# transmitter.net
KiCad netlist of a schematic drawn in EAGLE
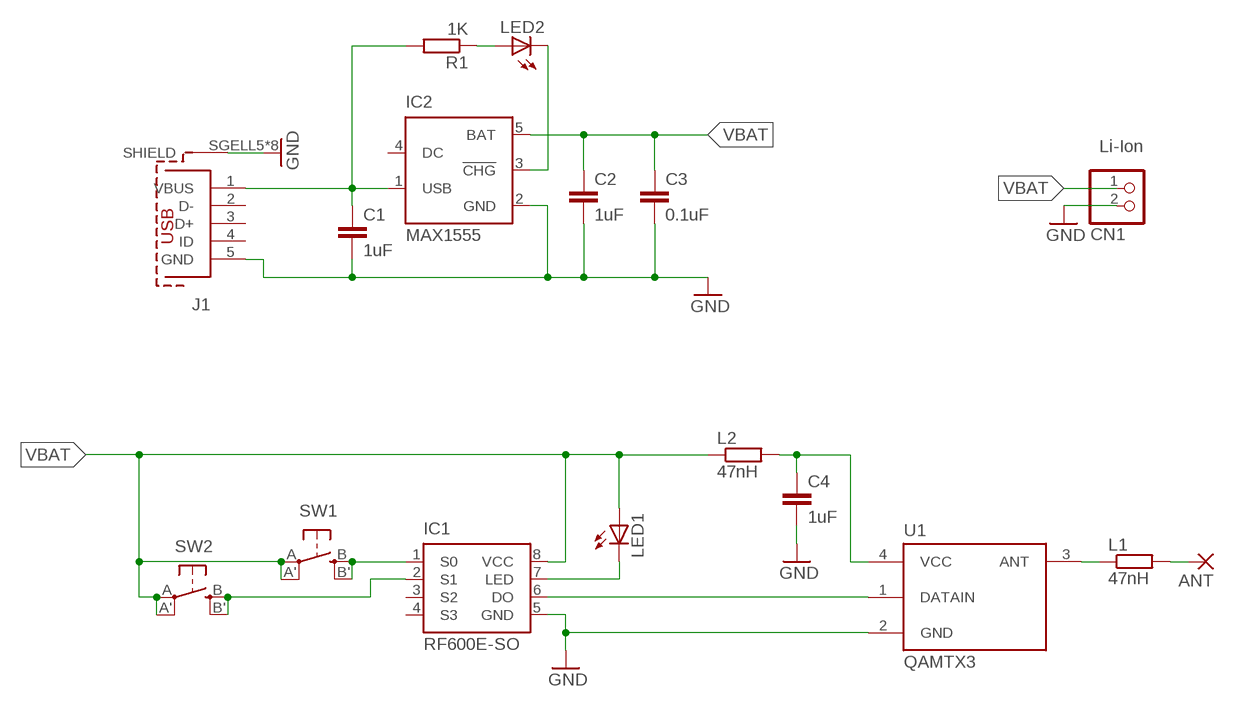
[diagram p0: schematic, sheet 1]

(export (version "E")
  (design (tool "Eeschema 10.0.6"))
  (components
    (comp (ref "ANT")
      (value "SMD2")
      (footprint "eagle-import:SMD1,27-2,54")
      (libsource (lib "eagle-import") (part "SMD2"))
    )
    (comp (ref "C1")
      (value "1uF")
      (footprint "eagle-import:C0603K")
      (libsource (lib "eagle-import") (part "C-EUC0603K"))
    )
    (comp (ref "C2")
      (value "1uF")
      (footprint "eagle-import:C0603K")
      (libsource (lib "eagle-import") (part "C-EUC0603K"))
    )
    (comp (ref "C3")
      (value "0.1uF")
      (footprint "eagle-import:C0603K")
      (libsource (lib "eagle-import") (part "C-EUC0603K"))
    )
    (comp (ref "C4")
      (value "1uF")
      (footprint "eagle-import:C0603K")
      (libsource (lib "eagle-import") (part "C-EUC0603K"))
    )
    (comp (ref "CN1")
      (value "JST_2PIN-SMT-RA")
      (footprint "eagle-import:JST-PH-2-SMT-RA")
      (libsource (lib "eagle-import") (part "JST_2PIN-SMT-RA"))
    )
    (comp (ref "IC1")
      (value "RF600E-SO")
      (footprint "eagle-import:SO-08")
      (fields (field (name "MF") "FARNELL"))
      (libsource (lib "eagle-import") (part "RF600E-SO"))
    )
    (comp (ref "IC2")
      (value "MAX1555")
      (footprint "eagle-import:SOT23-5L")
      (fields (field (name "MF") "MAXIM") (field (name "MPN") "MAX1555EZK+T"))
      (libsource (lib "eagle-import") (part "MAX1555"))
    )
    (comp (ref "J1")
      (value "629105150921")
      (footprint "eagle-import:629105150921")
      (libsource (lib "eagle-import") (part "629105150921"))
    )
    (comp (ref "L1")
      (value "47nH")
      (footprint "eagle-import:R0603")
      (libsource (lib "eagle-import") (part "R-EU_R0603"))
    )
    (comp (ref "L2")
      (value "47nH")
      (footprint "eagle-import:R0603")
      (libsource (lib "eagle-import") (part "R-EU_R0603"))
    )
    (comp (ref "LED1")
      (value "LEDCHIP-LED0805")
      (footprint "eagle-import:CHIP-LED0805")
      (libsource (lib "eagle-import") (part "LEDCHIP-LED0805"))
    )
    (comp (ref "LED2")
      (value "LEDCHIP-LED0805")
      (footprint "eagle-import:CHIP-LED0805")
      (libsource (lib "eagle-import") (part "LEDCHIP-LED0805"))
    )
    (comp (ref "R1")
      (value "1K")
      (footprint "eagle-import:R0603")
      (libsource (lib "eagle-import") (part "R-EU_R0603"))
    )
    (comp (ref "SW1")
      (value "SPST_TACT-EVQQ2")
      (footprint "eagle-import:EVQ-Q2")
      (libsource (lib "eagle-import") (part "SPST_TACT-EVQQ2"))
    )
    (comp (ref "SW2")
      (value "SPST_TACT-EVQQ2")
      (footprint "eagle-import:EVQ-Q2")
      (libsource (lib "eagle-import") (part "SPST_TACT-EVQQ2"))
    )
    (comp (ref "U1")
      (value "QAMTX3")
      (footprint "eagle-import:QAM-TX3")
      (libsource (lib "eagle-import") (part "QAMTX3"))
    )
  )
  (nets
    (net (code "1") (name "GND") (class "Default")
      (node (ref "C1") (pin "2") (pinfunction "2_2") (pintype "passive"))
      (node (ref "C2") (pin "2") (pinfunction "2_2") (pintype "passive"))
      (node (ref "C3") (pin "2") (pinfunction "2_2") (pintype "passive"))
      (node (ref "C4") (pin "2") (pinfunction "2_2") (pintype "passive"))
      (node (ref "CN1") (pin "2") (pinfunction "1_2") (pintype "passive"))
      (node (ref "IC1") (pin "5") (pinfunction "GND_5") (pintype "power_in"))
      (node (ref "IC2") (pin "2") (pinfunction "GND_2") (pintype "power_in"))
      (node (ref "J1") (pin "5") (pinfunction "GND_5") (pintype "passive"))
      (node (ref "J1") (pin "SGELL5") (pinfunction "SHIELD_SGELL5") (pintype "passive"))
      (node (ref "J1") (pin "SHELL") (pinfunction "SHIELD_SHELL") (pintype "passive"))
      (node (ref "J1") (pin "SHELL1") (pinfunction "SHIELD_SHELL1") (pintype "passive"))
      (node (ref "J1") (pin "SHELL2") (pinfunction "SHIELD_SHELL2") (pintype "passive"))
      (node (ref "J1") (pin "SHELL3") (pinfunction "SHIELD_SHELL3") (pintype "passive"))
      (node (ref "J1") (pin "SHELL4") (pinfunction "SHIELD_SHELL4") (pintype "passive"))
      (node (ref "J1") (pin "SHELL6") (pinfunction "SHIELD_SHELL6") (pintype "passive"))
      (node (ref "J1") (pin "SHELL7") (pinfunction "SHIELD_SHELL7") (pintype "passive"))
      (node (ref "U1") (pin "2") (pinfunction "GND_2") (pintype "power_in"))
    )
    (net (code "2") (name "Net-(ANT-P)") (class "Default")
      (node (ref "ANT") (pin "1") (pinfunction "P_1") (pintype "passive"))
      (node (ref "L1") (pin "2") (pinfunction "2_2") (pintype "passive"))
    )
    (net (code "3") (name "Net-(IC1-DO)") (class "Default")
      (node (ref "IC1") (pin "6") (pinfunction "DO_6") (pintype "output"))
      (node (ref "U1") (pin "1") (pinfunction "DATAIN_1") (pintype "bidirectional"))
    )
    (net (code "4") (name "Net-(IC1-LED)") (class "Default")
      (node (ref "IC1") (pin "7") (pinfunction "LED_7") (pintype "output"))
      (node (ref "LED1") (pin "C") (pinfunction "C_C") (pintype "passive"))
    )
    (net (code "5") (name "Net-(IC1-S0)") (class "Default")
      (node (ref "IC1") (pin "1") (pinfunction "S0_1") (pintype "input"))
      (node (ref "SW1") (pin "B") (pinfunction "S_B") (pintype "passive"))
      (node (ref "SW1") (pin "B'") (pinfunction "S1_B'") (pintype "passive"))
    )
    (net (code "6") (name "Net-(IC1-S1)") (class "Default")
      (node (ref "IC1") (pin "2") (pinfunction "S1_2") (pintype "input"))
      (node (ref "SW2") (pin "B") (pinfunction "S_B") (pintype "passive"))
      (node (ref "SW2") (pin "B'") (pinfunction "S1_B'") (pintype "passive"))
    )
    (net (code "7") (name "Net-(IC2-USB)") (class "Default")
      (node (ref "C1") (pin "1") (pinfunction "1_1") (pintype "passive"))
      (node (ref "IC2") (pin "1") (pinfunction "USB_1") (pintype "input"))
      (node (ref "J1") (pin "1") (pinfunction "VBUS_1") (pintype "passive"))
      (node (ref "R1") (pin "2") (pinfunction "2_2") (pintype "passive"))
    )
    (net (code "8") (name "Net-(IC2-~{CHG})") (class "Default")
      (node (ref "IC2") (pin "3") (pinfunction "~{CHG}_3") (pintype "output"))
      (node (ref "LED2") (pin "C") (pinfunction "C_C") (pintype "passive"))
    )
    (net (code "9") (name "Net-(LED2-PadA)") (class "Default")
      (node (ref "LED2") (pin "A") (pinfunction "A_A") (pintype "passive"))
      (node (ref "R1") (pin "1") (pinfunction "1_1") (pintype "passive"))
    )
    (net (code "10") (name "Net-(U1-ANT)") (class "Default")
      (node (ref "L1") (pin "1") (pinfunction "1_1") (pintype "passive"))
      (node (ref "U1") (pin "3") (pinfunction "ANT_3") (pintype "output"))
    )
    (net (code "11") (name "Net-(U1-VCC)") (class "Default")
      (node (ref "C4") (pin "1") (pinfunction "1_1") (pintype "passive"))
      (node (ref "L2") (pin "2") (pinfunction "2_2") (pintype "passive"))
      (node (ref "U1") (pin "4") (pinfunction "VCC_4") (pintype "power_in"))
    )
    (net (code "12") (name "VBAT") (class "Default")
      (node (ref "C2") (pin "1") (pinfunction "1_1") (pintype "passive"))
      (node (ref "C3") (pin "1") (pinfunction "1_1") (pintype "passive"))
      (node (ref "CN1") (pin "1") (pinfunction "2_1") (pintype "passive"))
      (node (ref "IC1") (pin "8") (pinfunction "VCC_8") (pintype "power_in"))
      (node (ref "IC2") (pin "5") (pinfunction "BAT_5") (pintype "passive"))
      (node (ref "L2") (pin "1") (pinfunction "1_1") (pintype "passive"))
      (node (ref "LED1") (pin "A") (pinfunction "A_A") (pintype "passive"))
      (node (ref "SW1") (pin "A") (pinfunction "P_A") (pintype "passive"))
      (node (ref "SW1") (pin "A'") (pinfunction "P1_A'") (pintype "passive"))
      (node (ref "SW2") (pin "A") (pinfunction "P_A") (pintype "passive"))
      (node (ref "SW2") (pin "A'") (pinfunction "P1_A'") (pintype "passive"))
    )
    (net (code "13") (name "unconnected-(IC1-S2-Pad3)") (class "Default")
      (node (ref "IC1") (pin "3") (pinfunction "S2_3") (pintype "input"))
    )
    (net (code "14") (name "unconnected-(IC1-S3-Pad4)") (class "Default")
      (node (ref "IC1") (pin "4") (pinfunction "S3_4") (pintype "input"))
    )
    (net (code "15") (name "unconnected-(IC2-DC-Pad4)") (class "Default")
      (node (ref "IC2") (pin "4") (pinfunction "DC_4") (pintype "input"))
    )
    (net (code "16") (name "unconnected-(J1-D+-Pad3)") (class "Default")
      (node (ref "J1") (pin "3") (pinfunction "D+_3") (pintype "passive"))
    )
    (net (code "17") (name "unconnected-(J1-D--Pad2)") (class "Default")
      (node (ref "J1") (pin "2") (pinfunction "D-_2") (pintype "passive"))
    )
    (net (code "18") (name "unconnected-(J1-ID-Pad4)") (class "Default")
      (node (ref "J1") (pin "4") (pinfunction "ID_4") (pintype "passive"))
    )
  )
)
